# Naked_Mega_I-b.net
KiCad netlist of a schematic drawn in EAGLE
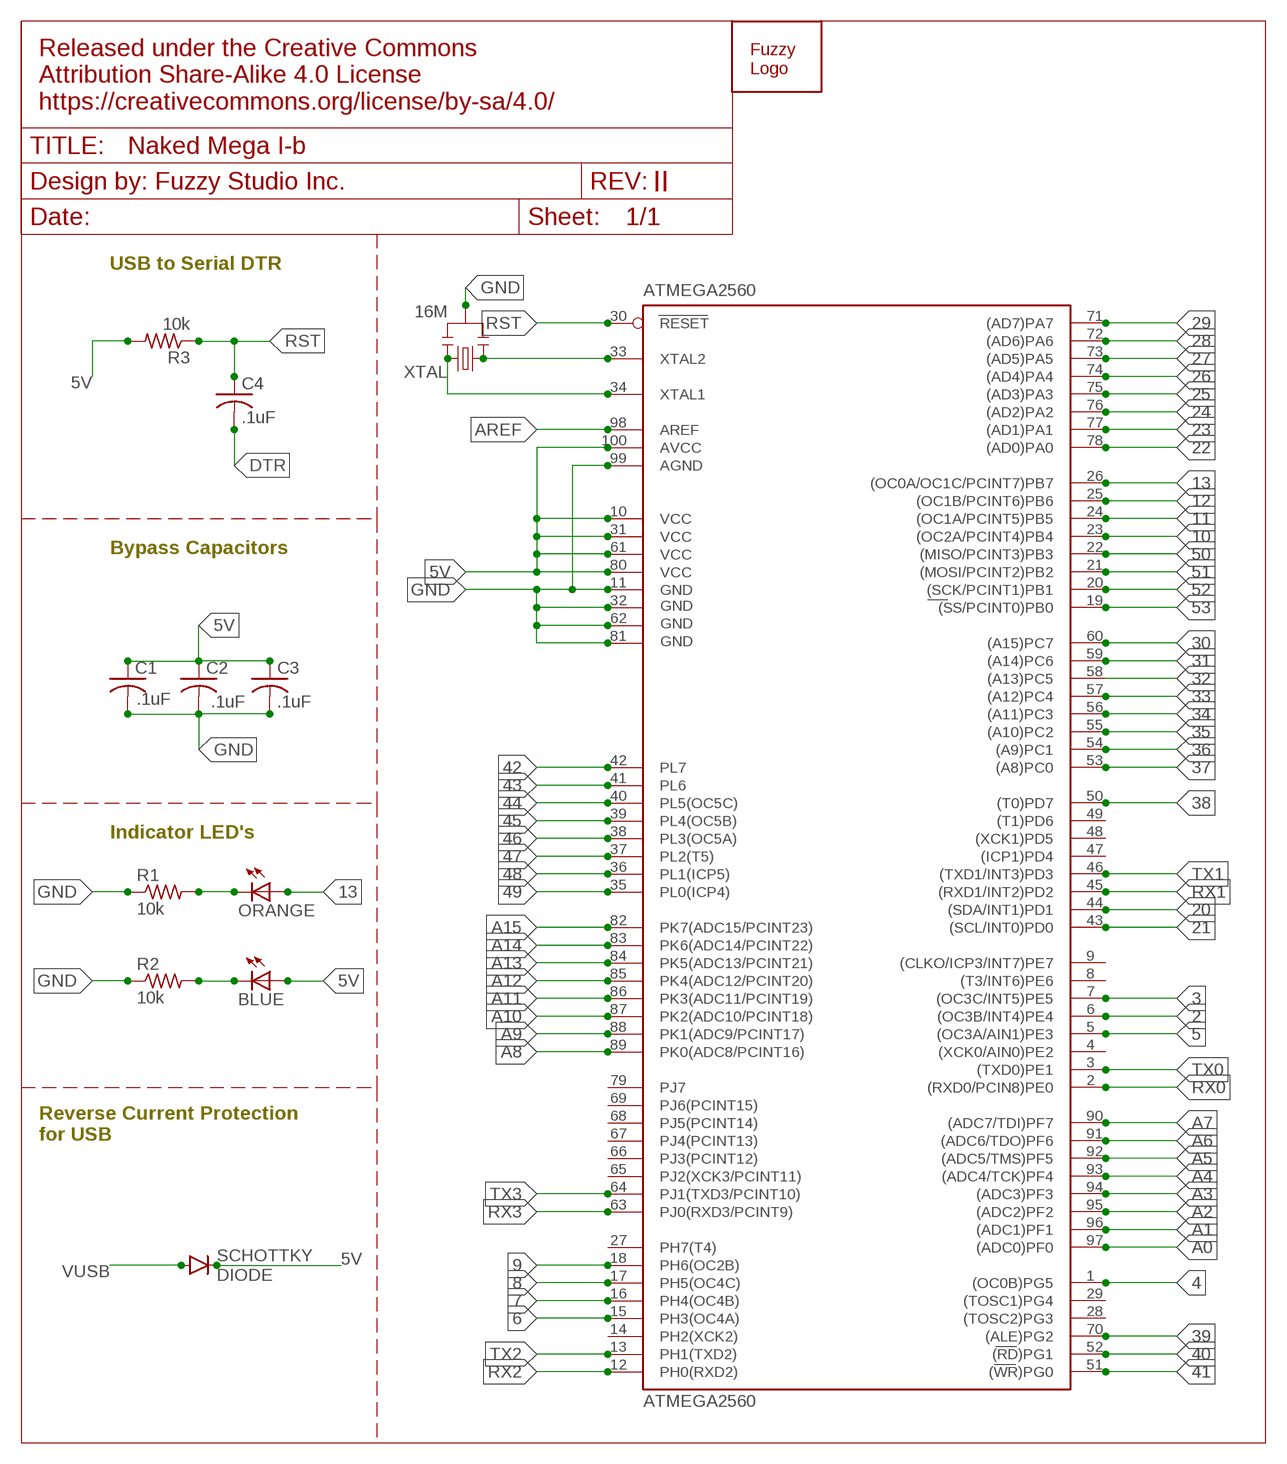
[diagram p0: schematic, sheet 1]

(export (version "E")
  (design (tool "Eeschema 10.0.6"))
  (components
    (comp (ref "ATMEGA2560")
      (value "ATMEGA2560")
      (footprint "eagle-import:TQFP100")
      (libsource (lib "eagle-import") (part "ATMEGA2560"))
    )
    (comp (ref "BLUE")
      (value "L")
      (footprint "eagle-import:SMD-0805-LED")
      (libsource (lib "eagle-import") (part "LED-SMD-0805"))
    )
    (comp (ref "C1")
      (value "CAPACITOR-SMD-0805")
      (footprint "eagle-import:SMD-0805")
      (libsource (lib "eagle-import") (part "CAPACITOR-SMD-0805"))
    )
    (comp (ref "C2")
      (value ".1uF")
      (footprint "eagle-import:SMD-0805")
      (libsource (lib "eagle-import") (part "CAPACITOR-SMD-0805"))
    )
    (comp (ref "C3")
      (value ".1uF")
      (footprint "eagle-import:SMD-0805")
      (libsource (lib "eagle-import") (part "CAPACITOR-SMD-0805"))
    )
    (comp (ref "C4")
      (value ".1uF")
      (footprint "eagle-import:SMD-0805")
      (libsource (lib "eagle-import") (part "CAPACITOR-SMD-0805"))
    )
    (comp (ref "ORANGE")
      (value "L")
      (footprint "eagle-import:SMD-0805-LED")
      (libsource (lib "eagle-import") (part "LED-SMD-0805"))
    )
    (comp (ref "R1")
      (value "10k")
      (footprint "eagle-import:SMD-0805")
      (libsource (lib "eagle-import") (part "RESISTOR-SMD-0805"))
    )
    (comp (ref "R2")
      (value "10k")
      (footprint "eagle-import:SMD-0805")
      (libsource (lib "eagle-import") (part "RESISTOR-SMD-0805"))
    )
    (comp (ref "R3")
      (value "10k")
      (footprint "eagle-import:SMD-0805")
      (libsource (lib "eagle-import") (part "RESISTOR-SMD-0805"))
    )
    (comp (ref "SCHOTTKY")
      (value "DIODE")
      (footprint "eagle-import:SOD-323")
      (libsource (lib "eagle-import") (part "DIODE"))
    )
    (comp (ref "U$1")
      (value "LOGO")
      (footprint "eagle-import:LOGO-S")
      (libsource (lib "eagle-import") (part "LOGO"))
    )
    (comp (ref "U$3")
      (value "DOCFRAME")
      (footprint "eagle-import:CREATIVECOMMONS")
      (libsource (lib "eagle-import") (part "DOCFRAME"))
    )
    (comp (ref "XTAL")
      (value "16M")
      (footprint "eagle-import:RESONATOR")
      (libsource (lib "eagle-import") (part "RESONATOR"))
    )
  )
  (nets
    (net (code "1") (name "/VUSB") (class "Default")
      (node (ref "SCHOTTKY") (pin "A") (pinfunction "A_A") (pintype "passive"))
    )
    (net (code "2") (name "2") (class "Default")
      (node (ref "ATMEGA2560") (pin "6") (pinfunction "(OC3B/INT4)PE4_6") (pintype "bidirectional"))
    )
    (net (code "3") (name "3") (class "Default")
      (node (ref "ATMEGA2560") (pin "7") (pinfunction "(OC3C/INT5)PE5_7") (pintype "bidirectional"))
    )
    (net (code "4") (name "4") (class "Default")
      (node (ref "ATMEGA2560") (pin "1") (pinfunction "(OC0B)PG5_1") (pintype "bidirectional"))
    )
    (net (code "5") (name "5") (class "Default")
      (node (ref "ATMEGA2560") (pin "5") (pinfunction "(OC3A/AIN1)PE3_5") (pintype "bidirectional"))
    )
    (net (code "6") (name "5V") (class "Default")
      (node (ref "ATMEGA2560") (pin "10") (pinfunction "VCC_10") (pintype "power_in"))
      (node (ref "ATMEGA2560") (pin "100") (pinfunction "AVCC_100") (pintype "power_in"))
      (node (ref "ATMEGA2560") (pin "31") (pinfunction "VCC1_31") (pintype "power_in"))
      (node (ref "ATMEGA2560") (pin "61") (pinfunction "VCC2_61") (pintype "power_in"))
      (node (ref "ATMEGA2560") (pin "80") (pinfunction "VCC3_80") (pintype "power_in"))
      (node (ref "BLUE") (pin "1") (pinfunction "A_1") (pintype "passive"))
      (node (ref "C1") (pin "1") (pinfunction "1_1") (pintype "passive"))
      (node (ref "C2") (pin "1") (pinfunction "1_1") (pintype "passive"))
      (node (ref "C3") (pin "1") (pinfunction "1_1") (pintype "passive"))
      (node (ref "R3") (pin "2") (pinfunction "2_2") (pintype "passive"))
      (node (ref "SCHOTTKY") (pin "C") (pinfunction "C_C") (pintype "passive"))
    )
    (net (code "7") (name "6") (class "Default")
      (node (ref "ATMEGA2560") (pin "15") (pinfunction "PH3(OC4A)_15") (pintype "bidirectional"))
    )
    (net (code "8") (name "7") (class "Default")
      (node (ref "ATMEGA2560") (pin "16") (pinfunction "PH4(OC4B)_16") (pintype "bidirectional"))
    )
    (net (code "9") (name "8") (class "Default")
      (node (ref "ATMEGA2560") (pin "17") (pinfunction "PH5(OC4C)_17") (pintype "bidirectional"))
    )
    (net (code "10") (name "9") (class "Default")
      (node (ref "ATMEGA2560") (pin "18") (pinfunction "PH6(OC2B)_18") (pintype "bidirectional"))
    )
    (net (code "11") (name "10") (class "Default")
      (node (ref "ATMEGA2560") (pin "23") (pinfunction "(OC2A/PCINT4)PB4_23") (pintype "bidirectional"))
    )
    (net (code "12") (name "11") (class "Default")
      (node (ref "ATMEGA2560") (pin "24") (pinfunction "(OC1A/PCINT5)PB5_24") (pintype "bidirectional"))
    )
    (net (code "13") (name "12") (class "Default")
      (node (ref "ATMEGA2560") (pin "25") (pinfunction "(OC1B/PCINT6)PB6_25") (pintype "bidirectional"))
    )
    (net (code "14") (name "13") (class "Default")
      (node (ref "ATMEGA2560") (pin "26") (pinfunction "(OC0A/OC1C/PCINT7)PB7_26") (pintype "bidirectional"))
      (node (ref "ORANGE") (pin "1") (pinfunction "A_1") (pintype "passive"))
    )
    (net (code "15") (name "20") (class "Default")
      (node (ref "ATMEGA2560") (pin "44") (pinfunction "(SDA/INT1)PD1_44") (pintype "bidirectional"))
    )
    (net (code "16") (name "21") (class "Default")
      (node (ref "ATMEGA2560") (pin "43") (pinfunction "(SCL/INT0)PD0_43") (pintype "bidirectional"))
    )
    (net (code "17") (name "22") (class "Default")
      (node (ref "ATMEGA2560") (pin "78") (pinfunction "(AD0)PA0_78") (pintype "bidirectional"))
    )
    (net (code "18") (name "23") (class "Default")
      (node (ref "ATMEGA2560") (pin "77") (pinfunction "(AD1)PA1_77") (pintype "bidirectional"))
    )
    (net (code "19") (name "24") (class "Default")
      (node (ref "ATMEGA2560") (pin "76") (pinfunction "(AD2)PA2_76") (pintype "bidirectional"))
    )
    (net (code "20") (name "25") (class "Default")
      (node (ref "ATMEGA2560") (pin "75") (pinfunction "(AD3)PA3_75") (pintype "bidirectional"))
    )
    (net (code "21") (name "26") (class "Default")
      (node (ref "ATMEGA2560") (pin "74") (pinfunction "(AD4)PA4_74") (pintype "bidirectional"))
    )
    (net (code "22") (name "27") (class "Default")
      (node (ref "ATMEGA2560") (pin "73") (pinfunction "(AD5)PA5_73") (pintype "bidirectional"))
    )
    (net (code "23") (name "28") (class "Default")
      (node (ref "ATMEGA2560") (pin "72") (pinfunction "(AD6)PA6_72") (pintype "bidirectional"))
    )
    (net (code "24") (name "29") (class "Default")
      (node (ref "ATMEGA2560") (pin "71") (pinfunction "(AD7)PA7_71") (pintype "bidirectional"))
    )
    (net (code "25") (name "30") (class "Default")
      (node (ref "ATMEGA2560") (pin "60") (pinfunction "(A15)PC7_60") (pintype "bidirectional"))
    )
    (net (code "26") (name "31") (class "Default")
      (node (ref "ATMEGA2560") (pin "59") (pinfunction "(A14)PC6_59") (pintype "bidirectional"))
    )
    (net (code "27") (name "32") (class "Default")
      (node (ref "ATMEGA2560") (pin "58") (pinfunction "(A13)PC5_58") (pintype "bidirectional"))
    )
    (net (code "28") (name "33") (class "Default")
      (node (ref "ATMEGA2560") (pin "57") (pinfunction "(A12)PC4_57") (pintype "bidirectional"))
    )
    (net (code "29") (name "34") (class "Default")
      (node (ref "ATMEGA2560") (pin "56") (pinfunction "(A11)PC3_56") (pintype "bidirectional"))
    )
    (net (code "30") (name "35") (class "Default")
      (node (ref "ATMEGA2560") (pin "55") (pinfunction "(A10)PC2_55") (pintype "bidirectional"))
    )
    (net (code "31") (name "36") (class "Default")
      (node (ref "ATMEGA2560") (pin "54") (pinfunction "(A9)PC1_54") (pintype "bidirectional"))
    )
    (net (code "32") (name "37") (class "Default")
      (node (ref "ATMEGA2560") (pin "53") (pinfunction "(A8)PC0_53") (pintype "bidirectional"))
    )
    (net (code "33") (name "38") (class "Default")
      (node (ref "ATMEGA2560") (pin "50") (pinfunction "(T0)PD7_50") (pintype "bidirectional"))
    )
    (net (code "34") (name "39") (class "Default")
      (node (ref "ATMEGA2560") (pin "70") (pinfunction "(ALE)PG2_70") (pintype "bidirectional"))
    )
    (net (code "35") (name "40") (class "Default")
      (node (ref "ATMEGA2560") (pin "52") (pinfunction "(RD)PG1_52") (pintype "bidirectional"))
    )
    (net (code "36") (name "41") (class "Default")
      (node (ref "ATMEGA2560") (pin "51") (pinfunction "(WR)PG0_51") (pintype "bidirectional"))
    )
    (net (code "37") (name "42") (class "Default")
      (node (ref "ATMEGA2560") (pin "42") (pinfunction "PL7_42") (pintype "bidirectional"))
    )
    (net (code "38") (name "43") (class "Default")
      (node (ref "ATMEGA2560") (pin "41") (pinfunction "PL6_41") (pintype "bidirectional"))
    )
    (net (code "39") (name "44") (class "Default")
      (node (ref "ATMEGA2560") (pin "40") (pinfunction "PL5(OC5C)_40") (pintype "bidirectional"))
    )
    (net (code "40") (name "45") (class "Default")
      (node (ref "ATMEGA2560") (pin "39") (pinfunction "PL4(OC5B)_39") (pintype "bidirectional"))
    )
    (net (code "41") (name "46") (class "Default")
      (node (ref "ATMEGA2560") (pin "38") (pinfunction "PL3(OC5A)_38") (pintype "bidirectional"))
    )
    (net (code "42") (name "47") (class "Default")
      (node (ref "ATMEGA2560") (pin "37") (pinfunction "PL2(T5)_37") (pintype "bidirectional"))
    )
    (net (code "43") (name "48") (class "Default")
      (node (ref "ATMEGA2560") (pin "36") (pinfunction "PL1(ICP5)_36") (pintype "bidirectional"))
    )
    (net (code "44") (name "49") (class "Default")
      (node (ref "ATMEGA2560") (pin "35") (pinfunction "PL0(ICP4)_35") (pintype "bidirectional"))
    )
    (net (code "45") (name "50") (class "Default")
      (node (ref "ATMEGA2560") (pin "22") (pinfunction "(MISO/PCINT3)PB3_22") (pintype "bidirectional"))
    )
    (net (code "46") (name "51") (class "Default")
      (node (ref "ATMEGA2560") (pin "21") (pinfunction "(MOSI/PCINT2)PB2_21") (pintype "bidirectional"))
    )
    (net (code "47") (name "52") (class "Default")
      (node (ref "ATMEGA2560") (pin "20") (pinfunction "(SCK/PCINT1)PB1_20") (pintype "bidirectional"))
    )
    (net (code "48") (name "53") (class "Default")
      (node (ref "ATMEGA2560") (pin "19") (pinfunction "(SS/PCINT0)PB0_19") (pintype "bidirectional"))
    )
    (net (code "49") (name "A0") (class "Default")
      (node (ref "ATMEGA2560") (pin "97") (pinfunction "(ADC0)PF0_97") (pintype "bidirectional"))
    )
    (net (code "50") (name "A1") (class "Default")
      (node (ref "ATMEGA2560") (pin "96") (pinfunction "(ADC1)PF1_96") (pintype "bidirectional"))
    )
    (net (code "51") (name "A2") (class "Default")
      (node (ref "ATMEGA2560") (pin "95") (pinfunction "(ADC2)PF2_95") (pintype "bidirectional"))
    )
    (net (code "52") (name "A3") (class "Default")
      (node (ref "ATMEGA2560") (pin "94") (pinfunction "(ADC3)PF3_94") (pintype "bidirectional"))
    )
    (net (code "53") (name "A4") (class "Default")
      (node (ref "ATMEGA2560") (pin "93") (pinfunction "(ADC4/TCK)PF4_93") (pintype "bidirectional"))
    )
    (net (code "54") (name "A5") (class "Default")
      (node (ref "ATMEGA2560") (pin "92") (pinfunction "(ADC5/TMS)PF5_92") (pintype "bidirectional"))
    )
    (net (code "55") (name "A6") (class "Default")
      (node (ref "ATMEGA2560") (pin "91") (pinfunction "(ADC6/TDO)PF6_91") (pintype "bidirectional"))
    )
    (net (code "56") (name "A7") (class "Default")
      (node (ref "ATMEGA2560") (pin "90") (pinfunction "(ADC7/TDI)PF7_90") (pintype "bidirectional"))
    )
    (net (code "57") (name "A8") (class "Default")
      (node (ref "ATMEGA2560") (pin "89") (pinfunction "PK0(ADC8/PCINT16)_89") (pintype "bidirectional"))
    )
    (net (code "58") (name "A9") (class "Default")
      (node (ref "ATMEGA2560") (pin "88") (pinfunction "PK1(ADC9/PCINT17)_88") (pintype "bidirectional"))
    )
    (net (code "59") (name "A10") (class "Default")
      (node (ref "ATMEGA2560") (pin "87") (pinfunction "PK2(ADC10/PCINT18)_87") (pintype "bidirectional"))
    )
    (net (code "60") (name "A11") (class "Default")
      (node (ref "ATMEGA2560") (pin "86") (pinfunction "PK3(ADC11/PCINT19)_86") (pintype "bidirectional"))
    )
    (net (code "61") (name "A12") (class "Default")
      (node (ref "ATMEGA2560") (pin "85") (pinfunction "PK4(ADC12/PCINT20)_85") (pintype "bidirectional"))
    )
    (net (code "62") (name "A13") (class "Default")
      (node (ref "ATMEGA2560") (pin "84") (pinfunction "PK5(ADC13/PCINT21)_84") (pintype "bidirectional"))
    )
    (net (code "63") (name "A14") (class "Default")
      (node (ref "ATMEGA2560") (pin "83") (pinfunction "PK6(ADC14/PCINT22)_83") (pintype "bidirectional"))
    )
    (net (code "64") (name "A15") (class "Default")
      (node (ref "ATMEGA2560") (pin "82") (pinfunction "PK7(ADC15/PCINT23)_82") (pintype "bidirectional"))
    )
    (net (code "65") (name "AREF") (class "Default")
      (node (ref "ATMEGA2560") (pin "98") (pinfunction "AREF_98") (pintype "bidirectional"))
    )
    (net (code "66") (name "DTR") (class "Default")
      (node (ref "C4") (pin "2") (pinfunction "2_2") (pintype "passive"))
    )
    (net (code "67") (name "GND") (class "Default")
      (node (ref "ATMEGA2560") (pin "11") (pinfunction "GND_11") (pintype "power_in"))
      (node (ref "ATMEGA2560") (pin "32") (pinfunction "GND1_32") (pintype "power_in"))
      (node (ref "ATMEGA2560") (pin "62") (pinfunction "GND2_62") (pintype "power_in"))
      (node (ref "ATMEGA2560") (pin "81") (pinfunction "GND3_81") (pintype "power_in"))
      (node (ref "ATMEGA2560") (pin "99") (pinfunction "AGND_99") (pintype "power_in"))
      (node (ref "C1") (pin "2") (pinfunction "2_2") (pintype "passive"))
      (node (ref "C2") (pin "2") (pinfunction "2_2") (pintype "passive"))
      (node (ref "C3") (pin "2") (pinfunction "2_2") (pintype "passive"))
      (node (ref "R1") (pin "1") (pinfunction "1_1") (pintype "passive"))
      (node (ref "R2") (pin "1") (pinfunction "1_1") (pintype "passive"))
      (node (ref "XTAL") (pin "2") (pinfunction "2_2") (pintype "passive"))
    )
    (net (code "68") (name "Net-(ATMEGA2560-XTAL1)") (class "Default")
      (node (ref "ATMEGA2560") (pin "34") (pinfunction "XTAL1_34") (pintype "input"))
      (node (ref "XTAL") (pin "3") (pinfunction "3_3") (pintype "passive"))
    )
    (net (code "69") (name "Net-(ATMEGA2560-XTAL2)") (class "Default")
      (node (ref "ATMEGA2560") (pin "33") (pinfunction "XTAL2_33") (pintype "output"))
      (node (ref "XTAL") (pin "1") (pinfunction "1_1") (pintype "passive"))
    )
    (net (code "70") (name "Net-(BLUE-C)") (class "Default")
      (node (ref "BLUE") (pin "2") (pinfunction "C_2") (pintype "passive"))
      (node (ref "R2") (pin "2") (pinfunction "2_2") (pintype "passive"))
    )
    (net (code "71") (name "Net-(ORANGE-C)") (class "Default")
      (node (ref "ORANGE") (pin "2") (pinfunction "C_2") (pintype "passive"))
      (node (ref "R1") (pin "2") (pinfunction "2_2") (pintype "passive"))
    )
    (net (code "72") (name "RST") (class "Default")
      (node (ref "ATMEGA2560") (pin "30") (pinfunction "RESET_30") (pintype "input"))
      (node (ref "C4") (pin "1") (pinfunction "1_1") (pintype "passive"))
      (node (ref "R3") (pin "1") (pinfunction "1_1") (pintype "passive"))
    )
    (net (code "73") (name "RX0") (class "Default")
      (node (ref "ATMEGA2560") (pin "2") (pinfunction "(RXD0/PCIN8)PE0_2") (pintype "bidirectional"))
    )
    (net (code "74") (name "RX1") (class "Default")
      (node (ref "ATMEGA2560") (pin "45") (pinfunction "(RXD1/INT2)PD2_45") (pintype "bidirectional"))
    )
    (net (code "75") (name "RX2") (class "Default")
      (node (ref "ATMEGA2560") (pin "12") (pinfunction "PH0(RXD2)_12") (pintype "bidirectional"))
    )
    (net (code "76") (name "RX3") (class "Default")
      (node (ref "ATMEGA2560") (pin "63") (pinfunction "PJ0(RXD3/PCINT9)_63") (pintype "bidirectional"))
    )
    (net (code "77") (name "TX0") (class "Default")
      (node (ref "ATMEGA2560") (pin "3") (pinfunction "(TXD0)PE1_3") (pintype "bidirectional"))
    )
    (net (code "78") (name "TX1") (class "Default")
      (node (ref "ATMEGA2560") (pin "46") (pinfunction "(TXD1/INT3)PD3_46") (pintype "bidirectional"))
    )
    (net (code "79") (name "TX2") (class "Default")
      (node (ref "ATMEGA2560") (pin "13") (pinfunction "PH1(TXD2)_13") (pintype "bidirectional"))
    )
    (net (code "80") (name "TX3") (class "Default")
      (node (ref "ATMEGA2560") (pin "64") (pinfunction "PJ1(TXD3/PCINT10)_64") (pintype "bidirectional"))
    )
    (net (code "81") (name "unconnected-(ATMEGA2560-(CLKO{slash}ICP3{slash}INT7)PE7-Pad9)") (class "Default")
      (node (ref "ATMEGA2560") (pin "9") (pinfunction "(CLKO/ICP3/INT7)PE7_9") (pintype "bidirectional"))
    )
    (net (code "82") (name "unconnected-(ATMEGA2560-(ICP1)PD4-Pad47)") (class "Default")
      (node (ref "ATMEGA2560") (pin "47") (pinfunction "(ICP1)PD4_47") (pintype "bidirectional"))
    )
    (net (code "83") (name "unconnected-(ATMEGA2560-(T1)PD6-Pad49)") (class "Default")
      (node (ref "ATMEGA2560") (pin "49") (pinfunction "(T1)PD6_49") (pintype "bidirectional"))
    )
    (net (code "84") (name "unconnected-(ATMEGA2560-(T3{slash}INT6)PE6-Pad8)") (class "Default")
      (node (ref "ATMEGA2560") (pin "8") (pinfunction "(T3/INT6)PE6_8") (pintype "bidirectional"))
    )
    (net (code "85") (name "unconnected-(ATMEGA2560-(TOSC1)PG4-Pad29)") (class "Default")
      (node (ref "ATMEGA2560") (pin "29") (pinfunction "(TOSC1)PG4_29") (pintype "bidirectional"))
    )
    (net (code "86") (name "unconnected-(ATMEGA2560-(TOSC2)PG3-Pad28)") (class "Default")
      (node (ref "ATMEGA2560") (pin "28") (pinfunction "(TOSC2)PG3_28") (pintype "bidirectional"))
    )
    (net (code "87") (name "unconnected-(ATMEGA2560-(XCK0{slash}AIN0)PE2-Pad4)") (class "Default")
      (node (ref "ATMEGA2560") (pin "4") (pinfunction "(XCK0/AIN0)PE2_4") (pintype "bidirectional"))
    )
    (net (code "88") (name "unconnected-(ATMEGA2560-(XCK1)PD5-Pad48)") (class "Default")
      (node (ref "ATMEGA2560") (pin "48") (pinfunction "(XCK1)PD5_48") (pintype "bidirectional"))
    )
    (net (code "89") (name "unconnected-(ATMEGA2560-PH2(XCK2)-Pad14)") (class "Default")
      (node (ref "ATMEGA2560") (pin "14") (pinfunction "PH2(XCK2)_14") (pintype "bidirectional"))
    )
    (net (code "90") (name "unconnected-(ATMEGA2560-PH7(T4)-Pad27)") (class "Default")
      (node (ref "ATMEGA2560") (pin "27") (pinfunction "PH7(T4)_27") (pintype "bidirectional"))
    )
    (net (code "91") (name "unconnected-(ATMEGA2560-PJ2(XCK3{slash}PCINT11)-Pad65)") (class "Default")
      (node (ref "ATMEGA2560") (pin "65") (pinfunction "PJ2(XCK3/PCINT11)_65") (pintype "bidirectional"))
    )
    (net (code "92") (name "unconnected-(ATMEGA2560-PJ3(PCINT12)-Pad66)") (class "Default")
      (node (ref "ATMEGA2560") (pin "66") (pinfunction "PJ3(PCINT12)_66") (pintype "bidirectional"))
    )
    (net (code "93") (name "unconnected-(ATMEGA2560-PJ4(PCINT13)-Pad67)") (class "Default")
      (node (ref "ATMEGA2560") (pin "67") (pinfunction "PJ4(PCINT13)_67") (pintype "bidirectional"))
    )
    (net (code "94") (name "unconnected-(ATMEGA2560-PJ5(PCINT14)-Pad68)") (class "Default")
      (node (ref "ATMEGA2560") (pin "68") (pinfunction "PJ5(PCINT14)_68") (pintype "bidirectional"))
    )
    (net (code "95") (name "unconnected-(ATMEGA2560-PJ6(PCINT15)-Pad69)") (class "Default")
      (node (ref "ATMEGA2560") (pin "69") (pinfunction "PJ6(PCINT15)_69") (pintype "bidirectional"))
    )
    (net (code "96") (name "unconnected-(ATMEGA2560-PJ7-Pad79)") (class "Default")
      (node (ref "ATMEGA2560") (pin "79") (pinfunction "PJ7_79") (pintype "bidirectional"))
    )
  )
)
